# Sheet1.net
KiCad netlist of a schematic drawn in Altium Designer
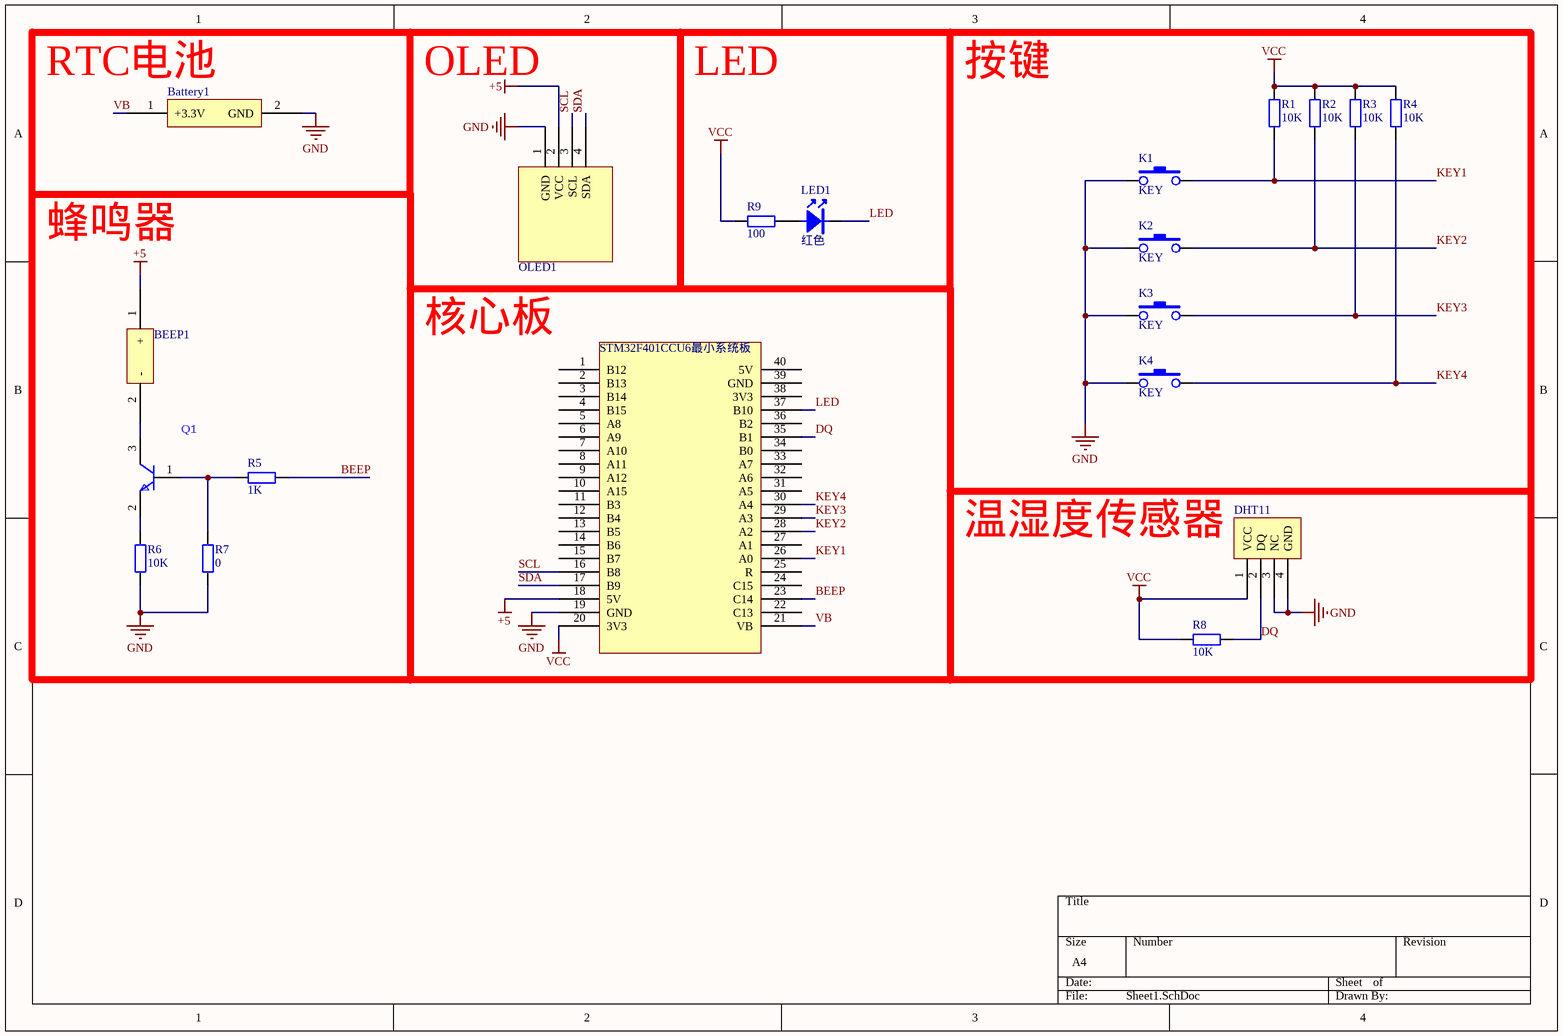
[diagram p0: Sheet1.SchDoc]

(export (version "E")
  (design (tool "Eeschema 10.0.6"))
  (components
    (comp (ref "Battery1")
      (value "Battery")
      (footprint "Battery")
      (libsource (lib "Schlib1") (part "Battery"))
    )
    (comp (ref "BEEP1") (value "BEEP") (footprint "BEEP") (libsource (lib "Schlib1") (part "BEEP")))
    (comp (ref "DHT11") (value "DHT11") (footprint "DHT11") (libsource (lib "Schlib1") (part "DHT11")))
    (comp (ref "K1")
      (value "KEY")
      (footprint "TSW DIP-6*6*5")
      (description "四角直插开关")
      (libsource (lib "03 - 按键-开关-晶振-蜂鸣器") (part "KEY"))
    )
    (comp (ref "K2")
      (value "KEY")
      (footprint "TSW DIP-6*6*5")
      (description "四角直插开关")
      (libsource (lib "03 - 按键-开关-晶振-蜂鸣器") (part "KEY"))
    )
    (comp (ref "K3")
      (value "KEY")
      (footprint "TSW DIP-6*6*5")
      (description "四角直插开关")
      (libsource (lib "03 - 按键-开关-晶振-蜂鸣器") (part "KEY"))
    )
    (comp (ref "K4")
      (value "KEY")
      (footprint "TSW DIP-6*6*5")
      (description "四角直插开关")
      (libsource (lib "03 - 按键-开关-晶振-蜂鸣器") (part "KEY"))
    )
    (comp (ref "LED1")
      (value "红色")
      (footprint "LED 0805G")
      (description "贴片LED")
      (libsource (lib "02 - 二极管(LED)-三极管-整流桥") (part "LED-SMD"))
    )
    (comp (ref "OLED1") (value "OLED") (footprint "OLED") (libsource (lib "Schlib1") (part "OLED")))
    (comp (ref "Q1")
      (value "~")
      (footprint "SOT-23")
      (libsource (lib "altium-import") (part "root_0_S9013LT1_"))
    )
    (comp (ref "R1")
      (value "10K")
      (footprint "R 0805_M")
      (description "贴片电阻")
      (libsource (lib "01 - 电容-电阻-电感") (part "R"))
    )
    (comp (ref "R2")
      (value "10K")
      (footprint "R 0805_M")
      (description "贴片电阻")
      (libsource (lib "01 - 电容-电阻-电感") (part "R"))
    )
    (comp (ref "R3")
      (value "10K")
      (footprint "R 0805_M")
      (description "贴片电阻")
      (libsource (lib "01 - 电容-电阻-电感") (part "R"))
    )
    (comp (ref "R4")
      (value "10K")
      (footprint "R 0805_M")
      (description "贴片电阻")
      (libsource (lib "01 - 电容-电阻-电感") (part "R"))
    )
    (comp (ref "R5")
      (value "1K")
      (footprint "R 0805_M")
      (description "贴片电阻")
      (libsource (lib "01 - 电容-电阻-电感") (part "R"))
    )
    (comp (ref "R6")
      (value "10K")
      (footprint "R 0805_M")
      (description "贴片电阻")
      (libsource (lib "01 - 电容-电阻-电感") (part "R"))
    )
    (comp (ref "R7")
      (value "0")
      (footprint "R 0805_M")
      (description "贴片电阻")
      (libsource (lib "01 - 电容-电阻-电感") (part "R"))
    )
    (comp (ref "R8")
      (value "10K")
      (footprint "R 0805_M")
      (description "贴片电阻")
      (libsource (lib "01 - 电容-电阻-电感") (part "R"))
    )
    (comp (ref "R9")
      (value "100")
      (footprint "R 0805_M")
      (description "贴片电阻")
      (libsource (lib "01 - 电容-电阻-电感") (part "R"))
    )
    (comp (ref "STM32F401CCU6最小系统板")
      (value "STM32F401CCU6最小系统板")
      (footprint "STM32F401CCU6")
      (libsource (lib "Schlib1") (part "STM32F401CCU6"))
    )
  )
  (nets
    (net (code "1") (name "+5") (class "Default")
      (node (ref "BEEP1") (pin "1") (pinfunction "+_1") (pintype "passive"))
      (node (ref "OLED1") (pin "2") (pinfunction "VCC_2") (pintype "passive"))
      (node (ref "STM32F401CCU6最小系统板") (pin "18") (pinfunction "5V_18") (pintype "passive"))
    )
    (net (code "2") (name "/BEEP") (class "Default")
      (node (ref "R5") (pin "2") (pinfunction "2_2") (pintype "passive"))
      (node (ref "STM32F401CCU6最小系统板") (pin "23") (pinfunction "C14_23") (pintype "passive"))
    )
    (net (code "3") (name "/DQ") (class "Default")
      (node (ref "DHT11") (pin "2") (pinfunction "DQ_2") (pintype "passive"))
      (node (ref "R8") (pin "1") (pinfunction "1_1") (pintype "passive"))
      (node (ref "STM32F401CCU6最小系统板") (pin "35") (pinfunction "B1_35") (pintype "passive"))
    )
    (net (code "4") (name "/KEY1") (class "Default")
      (node (ref "K1") (pin "2") (pinfunction "2_2") (pintype "passive"))
      (node (ref "R1") (pin "1") (pinfunction "1_1") (pintype "passive"))
      (node (ref "STM32F401CCU6最小系统板") (pin "26") (pinfunction "A0_26") (pintype "passive"))
    )
    (net (code "5") (name "/KEY2") (class "Default")
      (node (ref "K2") (pin "2") (pinfunction "2_2") (pintype "passive"))
      (node (ref "R2") (pin "1") (pinfunction "1_1") (pintype "passive"))
      (node (ref "STM32F401CCU6最小系统板") (pin "28") (pinfunction "A2_28") (pintype "passive"))
    )
    (net (code "6") (name "/KEY3") (class "Default")
      (node (ref "K3") (pin "2") (pinfunction "2_2") (pintype "passive"))
      (node (ref "R3") (pin "1") (pinfunction "1_1") (pintype "passive"))
      (node (ref "STM32F401CCU6最小系统板") (pin "29") (pinfunction "A3_29") (pintype "passive"))
    )
    (net (code "7") (name "/KEY4") (class "Default")
      (node (ref "K4") (pin "2") (pinfunction "2_2") (pintype "passive"))
      (node (ref "R4") (pin "1") (pinfunction "1_1") (pintype "passive"))
      (node (ref "STM32F401CCU6最小系统板") (pin "30") (pinfunction "A4_30") (pintype "passive"))
    )
    (net (code "8") (name "/LED") (class "Default")
      (node (ref "LED1") (pin "2") (pinfunction "K_2") (pintype "passive"))
      (node (ref "STM32F401CCU6最小系统板") (pin "37") (pinfunction "B10_37") (pintype "passive"))
    )
    (net (code "9") (name "/SCL") (class "Default")
      (node (ref "OLED1") (pin "3") (pinfunction "SCL_3") (pintype "passive"))
      (node (ref "STM32F401CCU6最小系统板") (pin "16") (pinfunction "B8_16") (pintype "passive"))
    )
    (net (code "10") (name "/SDA") (class "Default")
      (node (ref "OLED1") (pin "4") (pinfunction "SDA_4") (pintype "passive"))
      (node (ref "STM32F401CCU6最小系统板") (pin "17") (pinfunction "B9_17") (pintype "passive"))
    )
    (net (code "11") (name "/VB") (class "Default")
      (node (ref "Battery1") (pin "1") (pinfunction "+3.3V_1") (pintype "passive"))
      (node (ref "STM32F401CCU6最小系统板") (pin "21") (pinfunction "VB_21") (pintype "passive"))
    )
    (net (code "12") (name "GND") (class "Default")
      (node (ref "Battery1") (pin "2") (pinfunction "GND_2") (pintype "passive"))
      (node (ref "DHT11") (pin "3") (pinfunction "NC_3") (pintype "passive"))
      (node (ref "DHT11") (pin "4") (pinfunction "GND_4") (pintype "passive"))
      (node (ref "K1") (pin "1") (pinfunction "1_1") (pintype "passive"))
      (node (ref "K2") (pin "1") (pinfunction "1_1") (pintype "passive"))
      (node (ref "K3") (pin "1") (pinfunction "1_1") (pintype "passive"))
      (node (ref "K4") (pin "1") (pinfunction "1_1") (pintype "passive"))
      (node (ref "OLED1") (pin "1") (pinfunction "GND_1") (pintype "passive"))
      (node (ref "R6") (pin "1") (pinfunction "1_1") (pintype "passive"))
      (node (ref "R7") (pin "1") (pinfunction "1_1") (pintype "passive"))
      (node (ref "STM32F401CCU6最小系统板") (pin "19") (pinfunction "GND_19") (pintype "passive"))
    )
    (net (code "13") (name "Net-(BEEP1--)") (class "Default")
      (node (ref "BEEP1") (pin "2") (pinfunction "-_2") (pintype "passive"))
      (node (ref "Q1") (pin "3") (pinfunction "C_3") (pintype "passive"))
    )
    (net (code "14") (name "Net-(LED1-A)") (class "Default")
      (node (ref "LED1") (pin "1") (pinfunction "A_1") (pintype "passive"))
      (node (ref "R9") (pin "2") (pinfunction "2_2") (pintype "passive"))
    )
    (net (code "15") (name "Net-(Q1-B)") (class "Default")
      (node (ref "Q1") (pin "1") (pinfunction "B_1") (pintype "passive"))
      (node (ref "R5") (pin "1") (pinfunction "1_1") (pintype "passive"))
      (node (ref "R7") (pin "2") (pinfunction "2_2") (pintype "passive"))
    )
    (net (code "16") (name "Net-(Q1-E)") (class "Default")
      (node (ref "Q1") (pin "2") (pinfunction "E_2") (pintype "passive"))
      (node (ref "R6") (pin "2") (pinfunction "2_2") (pintype "passive"))
    )
    (net (code "17") (name "VCC") (class "Default")
      (node (ref "DHT11") (pin "1") (pinfunction "VCC_1") (pintype "passive"))
      (node (ref "R1") (pin "2") (pinfunction "2_2") (pintype "passive"))
      (node (ref "R2") (pin "2") (pinfunction "2_2") (pintype "passive"))
      (node (ref "R3") (pin "2") (pinfunction "2_2") (pintype "passive"))
      (node (ref "R4") (pin "2") (pinfunction "2_2") (pintype "passive"))
      (node (ref "R8") (pin "2") (pinfunction "2_2") (pintype "passive"))
      (node (ref "R9") (pin "1") (pinfunction "1_1") (pintype "passive"))
      (node (ref "STM32F401CCU6最小系统板") (pin "20") (pinfunction "3V3_20") (pintype "passive"))
    )
    (net (code "18") (name "unconnected-(STM32F401CCU6最小系统板-3V3-Pad38)") (class "Default")
      (node (ref "STM32F401CCU6最小系统板") (pin "38") (pinfunction "3V3_38") (pintype "passive"))
    )
    (net (code "19") (name "unconnected-(STM32F401CCU6最小系统板-5V-Pad40)") (class "Default")
      (node (ref "STM32F401CCU6最小系统板") (pin "40") (pinfunction "5V_40") (pintype "passive"))
    )
    (net (code "20") (name "unconnected-(STM32F401CCU6最小系统板-A1-Pad27)") (class "Default")
      (node (ref "STM32F401CCU6最小系统板") (pin "27") (pinfunction "A1_27") (pintype "passive"))
    )
    (net (code "21") (name "unconnected-(STM32F401CCU6最小系统板-A5-Pad31)") (class "Default")
      (node (ref "STM32F401CCU6最小系统板") (pin "31") (pinfunction "A5_31") (pintype "passive"))
    )
    (net (code "22") (name "unconnected-(STM32F401CCU6最小系统板-A6-Pad32)") (class "Default")
      (node (ref "STM32F401CCU6最小系统板") (pin "32") (pinfunction "A6_32") (pintype "passive"))
    )
    (net (code "23") (name "unconnected-(STM32F401CCU6最小系统板-A7-Pad33)") (class "Default")
      (node (ref "STM32F401CCU6最小系统板") (pin "33") (pinfunction "A7_33") (pintype "passive"))
    )
    (net (code "24") (name "unconnected-(STM32F401CCU6最小系统板-A8-Pad5)") (class "Default")
      (node (ref "STM32F401CCU6最小系统板") (pin "5") (pinfunction "A8_5") (pintype "passive"))
    )
    (net (code "25") (name "unconnected-(STM32F401CCU6最小系统板-A9-Pad6)") (class "Default")
      (node (ref "STM32F401CCU6最小系统板") (pin "6") (pinfunction "A9_6") (pintype "passive"))
    )
    (net (code "26") (name "unconnected-(STM32F401CCU6最小系统板-A10-Pad7)") (class "Default")
      (node (ref "STM32F401CCU6最小系统板") (pin "7") (pinfunction "A10_7") (pintype "passive"))
    )
    (net (code "27") (name "unconnected-(STM32F401CCU6最小系统板-A11-Pad8)") (class "Default")
      (node (ref "STM32F401CCU6最小系统板") (pin "8") (pinfunction "A11_8") (pintype "passive"))
    )
    (net (code "28") (name "unconnected-(STM32F401CCU6最小系统板-A12-Pad9)") (class "Default")
      (node (ref "STM32F401CCU6最小系统板") (pin "9") (pinfunction "A12_9") (pintype "passive"))
    )
    (net (code "29") (name "unconnected-(STM32F401CCU6最小系统板-A15-Pad10)") (class "Default")
      (node (ref "STM32F401CCU6最小系统板") (pin "10") (pinfunction "A15_10") (pintype "passive"))
    )
    (net (code "30") (name "unconnected-(STM32F401CCU6最小系统板-B0-Pad34)") (class "Default")
      (node (ref "STM32F401CCU6最小系统板") (pin "34") (pinfunction "B0_34") (pintype "passive"))
    )
    (net (code "31") (name "unconnected-(STM32F401CCU6最小系统板-B2-Pad36)") (class "Default")
      (node (ref "STM32F401CCU6最小系统板") (pin "36") (pinfunction "B2_36") (pintype "passive"))
    )
    (net (code "32") (name "unconnected-(STM32F401CCU6最小系统板-B3-Pad11)") (class "Default")
      (node (ref "STM32F401CCU6最小系统板") (pin "11") (pinfunction "B3_11") (pintype "passive"))
    )
    (net (code "33") (name "unconnected-(STM32F401CCU6最小系统板-B4-Pad12)") (class "Default")
      (node (ref "STM32F401CCU6最小系统板") (pin "12") (pinfunction "B4_12") (pintype "passive"))
    )
    (net (code "34") (name "unconnected-(STM32F401CCU6最小系统板-B5-Pad13)") (class "Default")
      (node (ref "STM32F401CCU6最小系统板") (pin "13") (pinfunction "B5_13") (pintype "passive"))
    )
    (net (code "35") (name "unconnected-(STM32F401CCU6最小系统板-B6-Pad14)") (class "Default")
      (node (ref "STM32F401CCU6最小系统板") (pin "14") (pinfunction "B6_14") (pintype "passive"))
    )
    (net (code "36") (name "unconnected-(STM32F401CCU6最小系统板-B7-Pad15)") (class "Default")
      (node (ref "STM32F401CCU6最小系统板") (pin "15") (pinfunction "B7_15") (pintype "passive"))
    )
    (net (code "37") (name "unconnected-(STM32F401CCU6最小系统板-B12-Pad1)") (class "Default")
      (node (ref "STM32F401CCU6最小系统板") (pin "1") (pinfunction "B12_1") (pintype "passive"))
    )
    (net (code "38") (name "unconnected-(STM32F401CCU6最小系统板-B13-Pad2)") (class "Default")
      (node (ref "STM32F401CCU6最小系统板") (pin "2") (pinfunction "B13_2") (pintype "passive"))
    )
    (net (code "39") (name "unconnected-(STM32F401CCU6最小系统板-B14-Pad3)") (class "Default")
      (node (ref "STM32F401CCU6最小系统板") (pin "3") (pinfunction "B14_3") (pintype "passive"))
    )
    (net (code "40") (name "unconnected-(STM32F401CCU6最小系统板-B15-Pad4)") (class "Default")
      (node (ref "STM32F401CCU6最小系统板") (pin "4") (pinfunction "B15_4") (pintype "passive"))
    )
    (net (code "41") (name "unconnected-(STM32F401CCU6最小系统板-C13-Pad22)") (class "Default")
      (node (ref "STM32F401CCU6最小系统板") (pin "22") (pinfunction "C13_22") (pintype "passive"))
    )
    (net (code "42") (name "unconnected-(STM32F401CCU6最小系统板-C15-Pad24)") (class "Default")
      (node (ref "STM32F401CCU6最小系统板") (pin "24") (pinfunction "C15_24") (pintype "passive"))
    )
    (net (code "43") (name "unconnected-(STM32F401CCU6最小系统板-GND-Pad39)") (class "Default")
      (node (ref "STM32F401CCU6最小系统板") (pin "39") (pinfunction "GND_39") (pintype "passive"))
    )
    (net (code "44") (name "unconnected-(STM32F401CCU6最小系统板-R-Pad25)") (class "Default")
      (node (ref "STM32F401CCU6最小系统板") (pin "25") (pinfunction "R_25") (pintype "passive"))
    )
  )
)
